# Sensor.net
KiCad netlist of a schematic drawn in Altium Designer
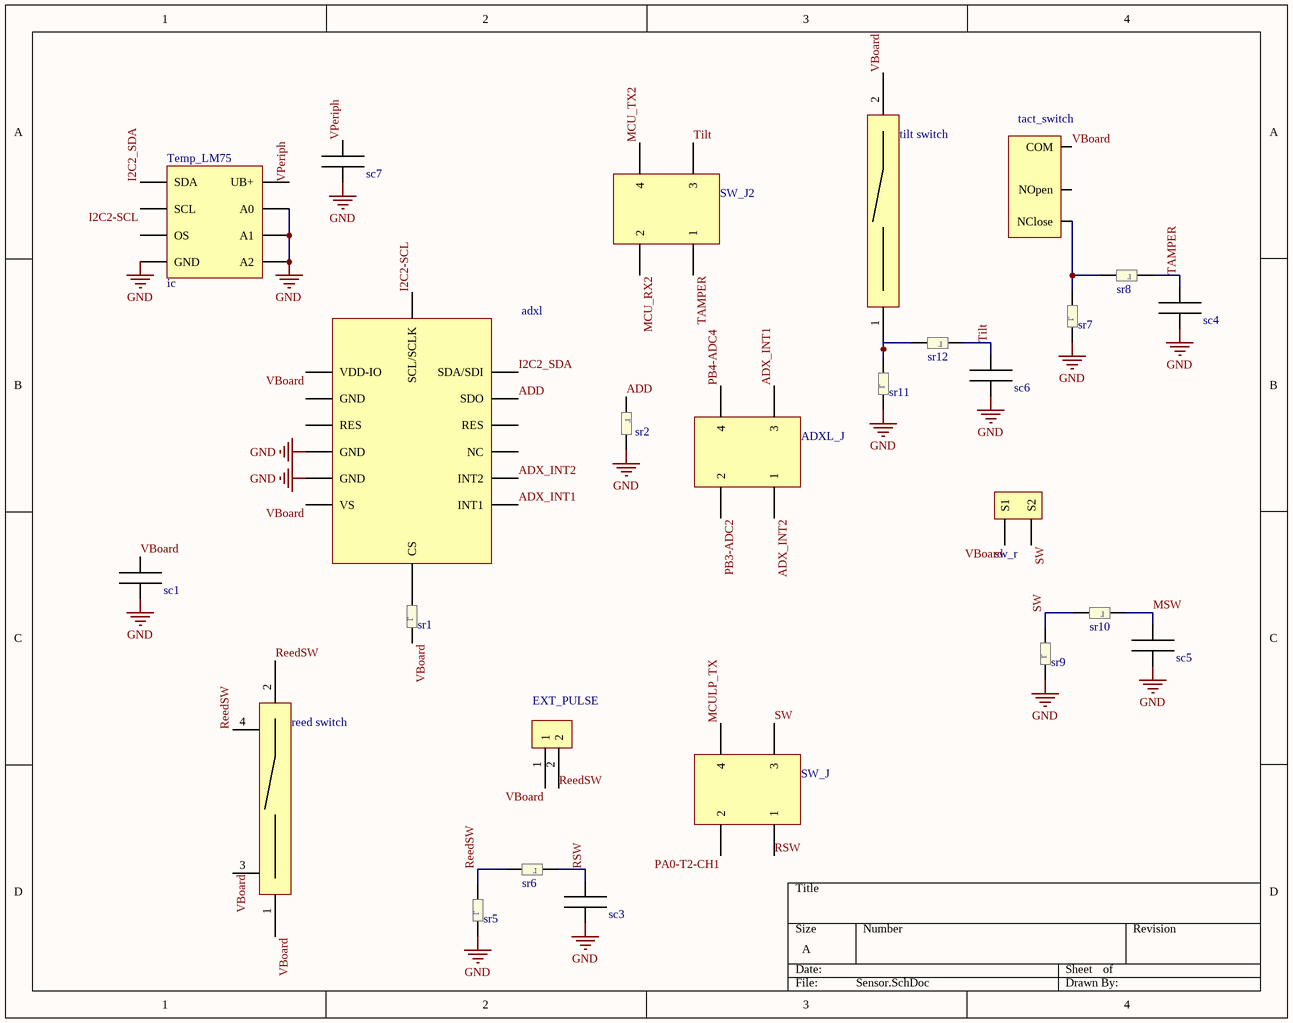
[diagram p0: Sensor.SchDoc]

(export (version "E")
  (design (tool "Eeschema 10.0.6"))
  (components
    (comp (ref "adxl")
      (value "ic")
      (footprint "abr_ic_adxl345_3d")
      (libsource (lib "abr_ic") (part "abr_ic_adxl345"))
    )
    (comp (ref "ADXL_J")
      (value "pin header 2mm")
      (footprint "abr_ph_2x2_2mm_3d_male")
      (libsource (lib "abr_ph_2mm_96_02") (part "abr_2x2_2mm"))
    )
    (comp (ref "EXT_PULSE")
      (value "YB2 SMD")
      (footprint "abr_sw_yb_2p_3d")
      (libsource (lib "lpwireless") (part "YB2 SMD"))
    )
    (comp (ref "reed switch")
      (value "switch")
      (footprint "abr_reed_sw_3d")
      (libsource (lib "abr_switch") (part "abr_reed_sw"))
    )
    (comp (ref "sc1")
      (value "100nf")
      (footprint "abr_cap_0805_3d")
      (libsource (lib "abr_smd_0805_all") (part "abr_cap_0805"))
    )
    (comp (ref "sc3")
      (value "100nf")
      (footprint "abr_cap_0805_3d")
      (libsource (lib "abr_smd_0805_all") (part "abr_cap_0805"))
    )
    (comp (ref "sc4")
      (value "100nf")
      (footprint "abr_cap_0805_3d")
      (libsource (lib "abr_smd_0805_all") (part "abr_cap_0805"))
    )
    (comp (ref "sc5")
      (value "100nf")
      (footprint "abr_cap_0805_3d")
      (libsource (lib "abr_smd_0805_all") (part "abr_cap_0805"))
    )
    (comp (ref "sc6")
      (value "100nf")
      (footprint "abr_cap_0805_3d")
      (libsource (lib "abr_smd_0805_all") (part "abr_cap_0805"))
    )
    (comp (ref "sc7")
      (value "100nf")
      (footprint "abr_cap_0805_3d")
      (libsource (lib "abr_smd_0805_all") (part "abr_cap_0805"))
    )
    (comp (ref "sr1")
      (value "100k")
      (footprint "abr_res_0805_3d")
      (libsource (lib "abr_smd_0805_all") (part "abr_res_0805"))
    )
    (comp (ref "sr2")
      (value "100k")
      (footprint "abr_res_0805_3d")
      (libsource (lib "") (part "abr_res_0805_2"))
    )
    (comp (ref "sr5")
      (value "2.2K")
      (footprint "abr_res_0805_3d")
      (libsource (lib "abr_smd_0805_all") (part "abr_res_0805"))
    )
    (comp (ref "sr6") (value "1k") (footprint "abr_res_0805_3d") (libsource (lib "") (part "abr_res_0805_1")))
    (comp (ref "sr7")
      (value "2.2K")
      (footprint "abr_res_0805_3d")
      (libsource (lib "abr_smd_0805_all") (part "abr_res_0805"))
    )
    (comp (ref "sr8") (value "1k") (footprint "abr_res_0805_3d") (libsource (lib "") (part "abr_res_0805_1")))
    (comp (ref "sr9")
      (value "2.2K")
      (footprint "abr_res_0805_3d")
      (libsource (lib "abr_smd_0805_all") (part "abr_res_0805"))
    )
    (comp (ref "sr10")
      (value "1k")
      (footprint "abr_res_0805_3d")
      (libsource (lib "") (part "abr_res_0805_1"))
    )
    (comp (ref "sr11")
      (value "2.2K")
      (footprint "abr_res_0805_3d")
      (libsource (lib "abr_smd_0805_all") (part "abr_res_0805"))
    )
    (comp (ref "sr12")
      (value "1k")
      (footprint "abr_res_0805_3d")
      (libsource (lib "") (part "abr_res_0805_1"))
    )
    (comp (ref "SW_J")
      (value "pin header 2mm")
      (footprint "abr_ph_2x2_2mm_3d_male")
      (libsource (lib "abr_ph_2mm_96_02") (part "abr_2x2_2mm"))
    )
    (comp (ref "SW_J2")
      (value "pin header 2mm")
      (footprint "abr_ph_2x2_2mm_3d_male")
      (libsource (lib "abr_ph_2mm_96_02") (part "abr_2x2_2mm"))
    )
    (comp (ref "sw_r")
      (value "switch")
      (footprint "abr_sw_tact_3d")
      (libsource (lib "abr_switch") (part "abr_switch_tact"))
    )
    (comp (ref "tact_switch")
      (value "switch")
      (footprint "abr_proximity_switch_3d")
      (libsource (lib "abr_switch") (part "abr_tact_switch"))
    )
    (comp (ref "Temp_LM75")
      (value "ic")
      (footprint "abr_ic_lm75_3d")
      (libsource (lib "abr_ic") (part "abr_ic_lm75"))
    )
    (comp (ref "tilt switch")
      (value "switch")
      (footprint "abr_tilt_horiz_sw200d_3d")
      (libsource (lib "abr_switch") (part "abr_tilt_sw"))
    )
  )
  (nets
    (net (code "1") (name "/ADD") (class "Default")
      (node (ref "adxl") (pin "12") (pinfunction "SDO_12") (pintype "passive"))
      (node (ref "sr2") (pin "0") (pinfunction "0_0") (pintype "passive"))
    )
    (net (code "2") (name "/ADX_INT1") (class "Default")
      (node (ref "ADXL_J") (pin "3") (pinfunction "3_3") (pintype "passive"))
      (node (ref "adxl") (pin "8") (pinfunction "INT1_8") (pintype "passive"))
    )
    (net (code "3") (name "/ADX_INT2") (class "Default")
      (node (ref "ADXL_J") (pin "1") (pinfunction "1_1") (pintype "passive"))
      (node (ref "adxl") (pin "9") (pinfunction "INT2_9") (pintype "passive"))
    )
    (net (code "4") (name "/I2C2-SCL") (class "Default")
      (node (ref "Temp_LM75") (pin "2") (pinfunction "SCL_2") (pintype "passive"))
      (node (ref "adxl") (pin "14") (pinfunction "SCL/SCLK_14") (pintype "passive"))
    )
    (net (code "5") (name "/I2C2_SDA") (class "Default")
      (node (ref "Temp_LM75") (pin "1") (pinfunction "SDA_1") (pintype "passive"))
      (node (ref "adxl") (pin "13") (pinfunction "SDA/SDI_13") (pintype "passive"))
    )
    (net (code "6") (name "/MCULP_TX") (class "Default")
      (node (ref "SW_J") (pin "4") (pinfunction "4_4") (pintype "passive"))
    )
    (net (code "7") (name "/MCU_RX2") (class "Default")
      (node (ref "SW_J2") (pin "2") (pinfunction "2_2") (pintype "passive"))
    )
    (net (code "8") (name "/MCU_TX2") (class "Default")
      (node (ref "SW_J2") (pin "4") (pinfunction "4_4") (pintype "passive"))
    )
    (net (code "9") (name "/MSW") (class "Default")
      (node (ref "sc5") (pin "1") (pinfunction "10_1") (pintype "passive"))
      (node (ref "sr10") (pin "0") (pinfunction "0_0") (pintype "passive"))
    )
    (net (code "10") (name "/PA0-T2-CH1") (class "Default")
      (node (ref "SW_J") (pin "2") (pinfunction "2_2") (pintype "passive"))
    )
    (net (code "11") (name "/PB3-ADC2") (class "Default")
      (node (ref "ADXL_J") (pin "2") (pinfunction "2_2") (pintype "passive"))
    )
    (net (code "12") (name "/PB4-ADC4") (class "Default")
      (node (ref "ADXL_J") (pin "4") (pinfunction "4_4") (pintype "passive"))
    )
    (net (code "13") (name "/RSW") (class "Default")
      (node (ref "SW_J") (pin "1") (pinfunction "1_1") (pintype "passive"))
      (node (ref "sc3") (pin "1") (pinfunction "10_1") (pintype "passive"))
      (node (ref "sr6") (pin "0") (pinfunction "0_0") (pintype "passive"))
    )
    (net (code "14") (name "/ReedSW") (class "Default")
      (node (ref "EXT_PULSE") (pin "2") (pinfunction "2_2") (pintype "passive"))
      (node (ref "reed switch") (pin "2") (pintype "passive"))
      (node (ref "reed switch") (pin "4") (pintype "passive"))
      (node (ref "sr5") (pin "1") (pinfunction "0_1") (pintype "passive"))
      (node (ref "sr6") (pin "1") (pinfunction "0_1") (pintype "passive"))
    )
    (net (code "15") (name "/SW") (class "Default")
      (node (ref "SW_J") (pin "3") (pinfunction "3_3") (pintype "passive"))
      (node (ref "sr10") (pin "1") (pinfunction "0_1") (pintype "passive"))
      (node (ref "sr9") (pin "1") (pinfunction "0_1") (pintype "passive"))
      (node (ref "sw_r") (pin "2") (pinfunction "S2_2") (pintype "passive"))
    )
    (net (code "16") (name "/TAMPER") (class "Default")
      (node (ref "SW_J2") (pin "1") (pinfunction "1_1") (pintype "passive"))
      (node (ref "sc4") (pin "1") (pinfunction "10_1") (pintype "passive"))
      (node (ref "sr8") (pin "0") (pinfunction "0_0") (pintype "passive"))
    )
    (net (code "17") (name "/Tilt") (class "Default")
      (node (ref "SW_J2") (pin "3") (pinfunction "3_3") (pintype "passive"))
      (node (ref "sc6") (pin "1") (pinfunction "10_1") (pintype "passive"))
      (node (ref "sr12") (pin "0") (pinfunction "0_0") (pintype "passive"))
    )
    (net (code "18") (name "/VBoard") (class "Default")
      (node (ref "EXT_PULSE") (pin "1") (pinfunction "1_1") (pintype "passive"))
      (node (ref "adxl") (pin "1") (pinfunction "VDD-IO_1") (pintype "passive"))
      (node (ref "adxl") (pin "6") (pinfunction "VS_6") (pintype "passive"))
      (node (ref "reed switch") (pin "1") (pintype "passive"))
      (node (ref "reed switch") (pin "3") (pintype "passive"))
      (node (ref "sc1") (pin "1") (pinfunction "10_1") (pintype "passive"))
      (node (ref "sr1") (pin "0") (pinfunction "0_0") (pintype "passive"))
      (node (ref "sw_r") (pin "1") (pinfunction "S1_1") (pintype "passive"))
      (node (ref "tact_switch") (pin "1") (pinfunction "COM_1") (pintype "passive"))
      (node (ref "tilt switch") (pin "2") (pintype "passive"))
    )
    (net (code "19") (name "/VPeriph") (class "Default")
      (node (ref "Temp_LM75") (pin "8") (pinfunction "UB+_8") (pintype "passive"))
      (node (ref "sc7") (pin "0") (pinfunction "2_0") (pintype "passive"))
    )
    (net (code "20") (name "GND") (class "Default")
      (node (ref "Temp_LM75") (pin "4") (pinfunction "GND_4") (pintype "passive"))
      (node (ref "Temp_LM75") (pin "5") (pinfunction "A2_5") (pintype "passive"))
      (node (ref "Temp_LM75") (pin "6") (pinfunction "A1_6") (pintype "passive"))
      (node (ref "Temp_LM75") (pin "7") (pinfunction "A0_7") (pintype "passive"))
      (node (ref "adxl") (pin "4") (pinfunction "GND_4") (pintype "passive"))
      (node (ref "adxl") (pin "5") (pinfunction "GND_5") (pintype "passive"))
      (node (ref "sc1") (pin "0") (pinfunction "2_0") (pintype "passive"))
      (node (ref "sc3") (pin "0") (pinfunction "2_0") (pintype "passive"))
      (node (ref "sc4") (pin "0") (pinfunction "2_0") (pintype "passive"))
      (node (ref "sc5") (pin "0") (pinfunction "2_0") (pintype "passive"))
      (node (ref "sc6") (pin "0") (pinfunction "2_0") (pintype "passive"))
      (node (ref "sc7") (pin "1") (pinfunction "10_1") (pintype "passive"))
      (node (ref "sr11") (pin "0") (pinfunction "0_0") (pintype "passive"))
      (node (ref "sr2") (pin "1") (pinfunction "0_1") (pintype "passive"))
      (node (ref "sr5") (pin "0") (pinfunction "0_0") (pintype "passive"))
      (node (ref "sr7") (pin "0") (pinfunction "0_0") (pintype "passive"))
      (node (ref "sr9") (pin "0") (pinfunction "0_0") (pintype "passive"))
    )
    (net (code "21") (name "Net-(adxl-CS)") (class "Default")
      (node (ref "adxl") (pin "7") (pinfunction "CS_7") (pintype "passive"))
      (node (ref "sr1") (pin "1") (pinfunction "0_1") (pintype "passive"))
    )
    (net (code "22") (name "Net-(sr11-0-Pad1)") (class "Default")
      (node (ref "sr11") (pin "1") (pinfunction "0_1") (pintype "passive"))
      (node (ref "sr12") (pin "1") (pinfunction "0_1") (pintype "passive"))
      (node (ref "tilt switch") (pin "1") (pintype "passive"))
    )
    (net (code "23") (name "Net-(tact_switch-NClose)") (class "Default")
      (node (ref "sr7") (pin "1") (pinfunction "0_1") (pintype "passive"))
      (node (ref "sr8") (pin "1") (pinfunction "0_1") (pintype "passive"))
      (node (ref "tact_switch") (pin "3") (pinfunction "NClose_3") (pintype "passive"))
    )
    (net (code "24") (name "unconnected-(Temp_LM75-OS-Pad3)") (class "Default")
      (node (ref "Temp_LM75") (pin "3") (pinfunction "OS_3") (pintype "passive"))
    )
    (net (code "25") (name "unconnected-(adxl-GND-Pad2)") (class "Default")
      (node (ref "adxl") (pin "2") (pinfunction "GND_2") (pintype "passive"))
    )
    (net (code "26") (name "unconnected-(adxl-NC-Pad10)") (class "Default")
      (node (ref "adxl") (pin "10") (pinfunction "NC_10") (pintype "passive"))
    )
    (net (code "27") (name "unconnected-(adxl-RES-Pad3)") (class "Default")
      (node (ref "adxl") (pin "3") (pinfunction "RES_3") (pintype "passive"))
    )
    (net (code "28") (name "unconnected-(adxl-RES-Pad11)") (class "Default")
      (node (ref "adxl") (pin "11") (pinfunction "RES_11") (pintype "passive"))
    )
    (net (code "29") (name "unconnected-(tact_switch-NOpen-Pad2)") (class "Default")
      (node (ref "tact_switch") (pin "2") (pinfunction "NOpen_2") (pintype "passive"))
    )
  )
)
